# BusAdaptor.net
KiCad netlist of a schematic drawn in Altium Designer
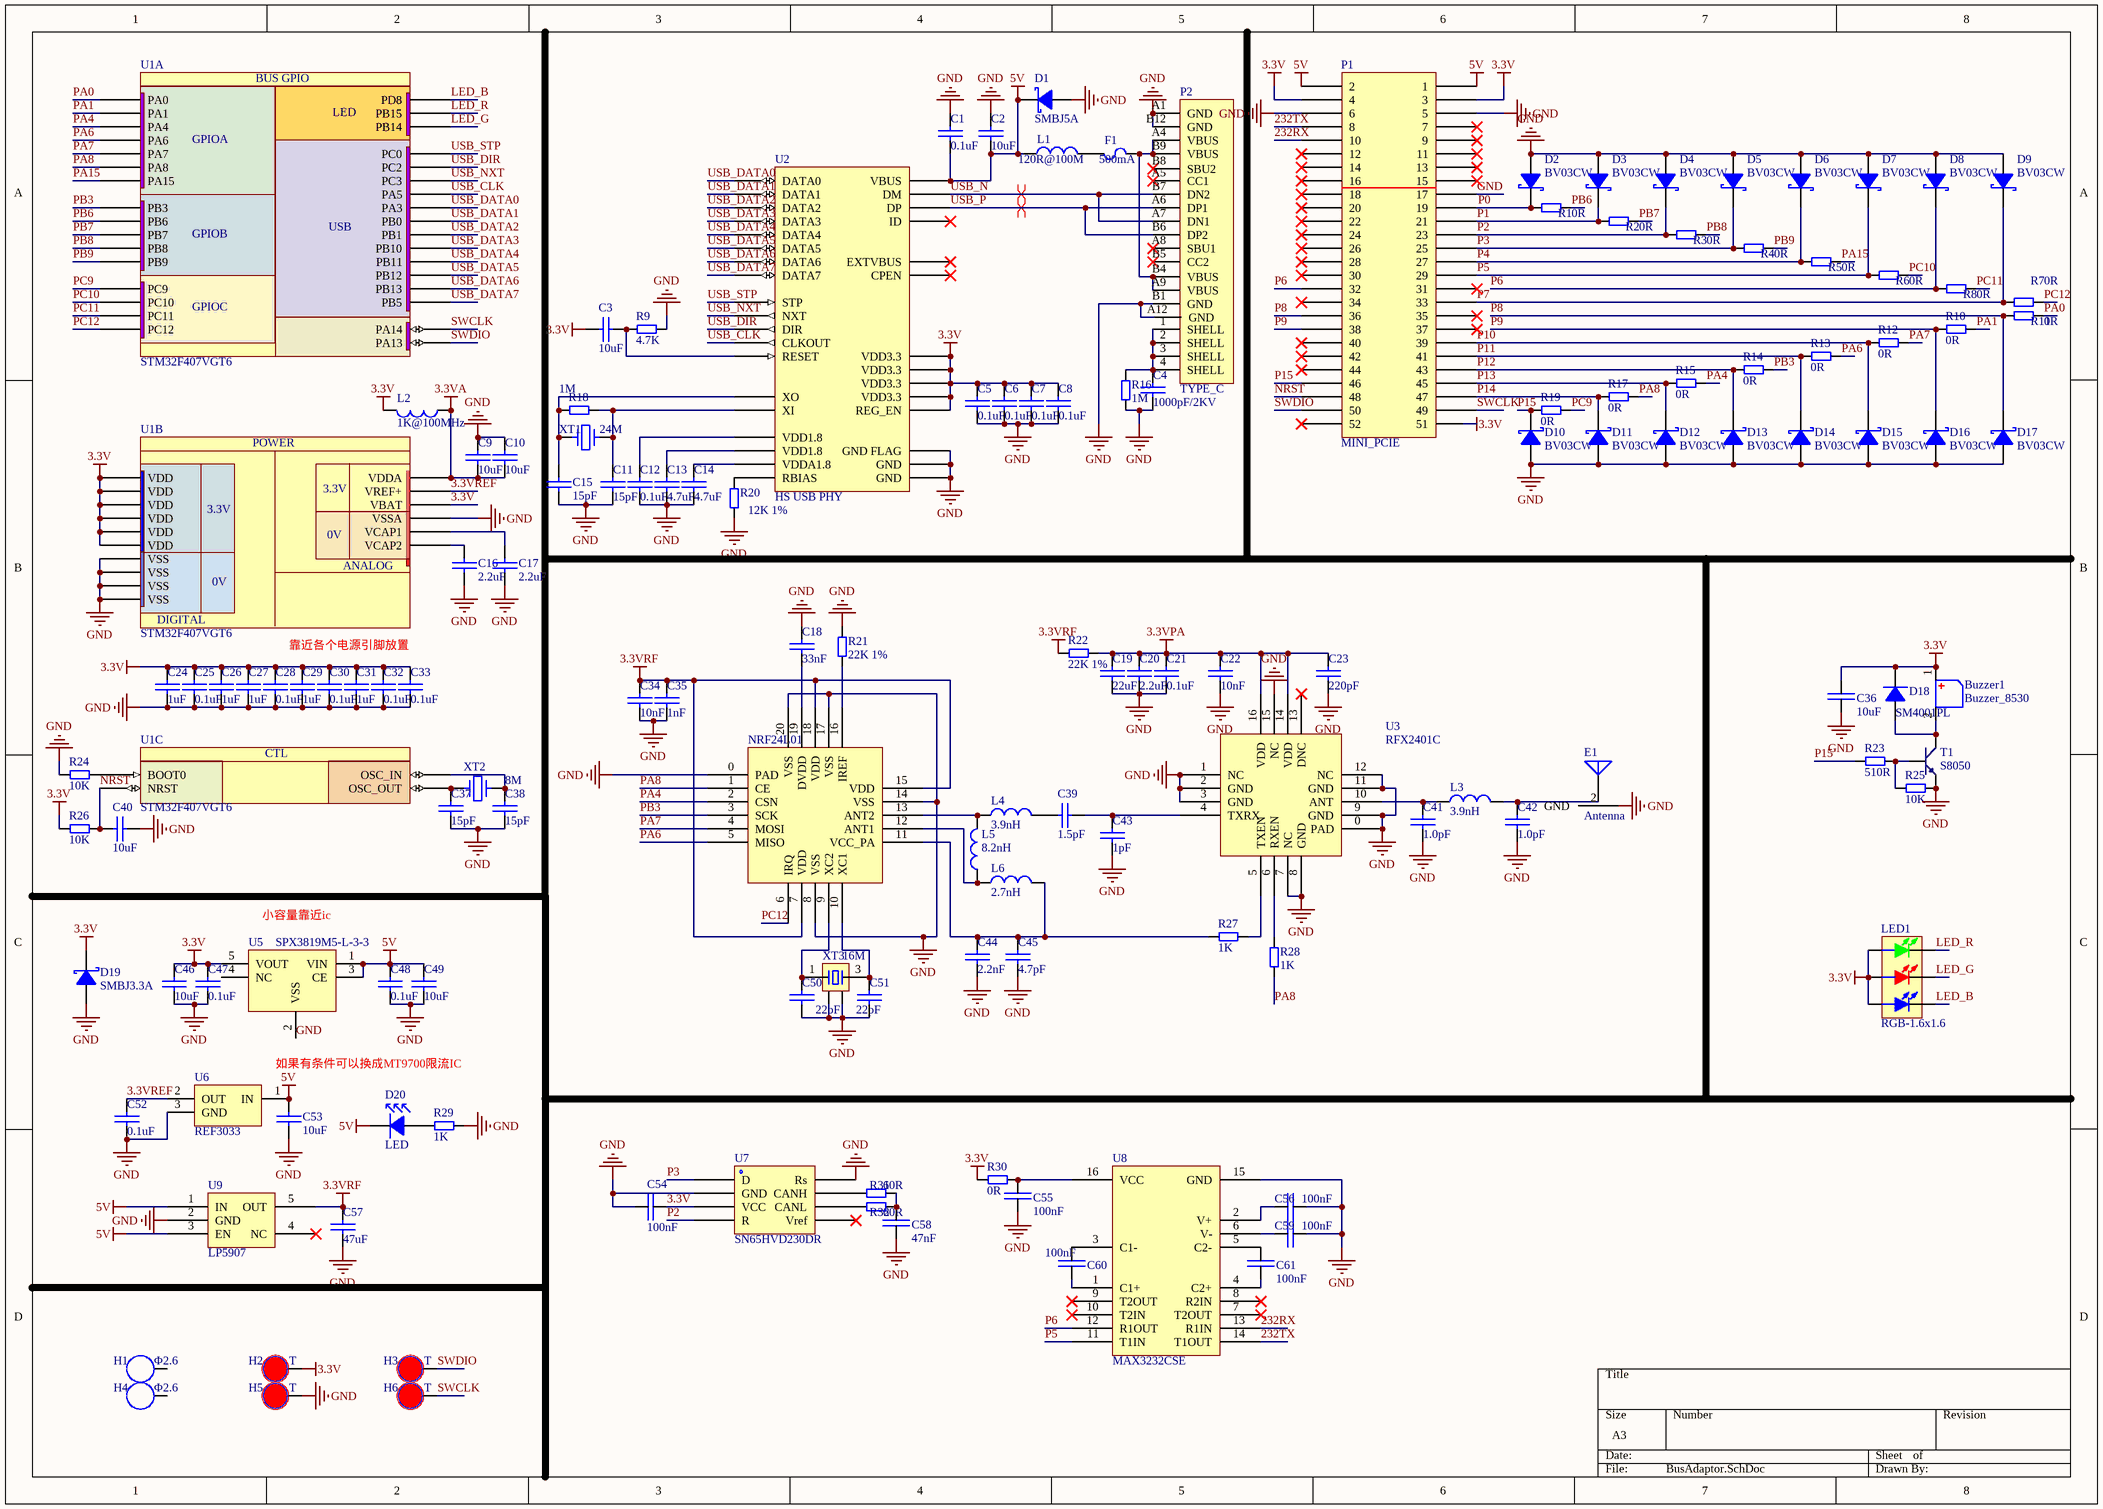
[diagram p0: BusAdaptor.SchDoc]

(export (version "E")
  (design (tool "Eeschema 10.0.6"))
  (components
    (comp (ref "Buzzer1")
      (value "Buzzer_8530")
      (footprint "BUZZER_8530")
      (description "无源蜂鸣器")
      (libsource (lib "BusAdaptor") (part "Buzzer_8530"))
    )
    (comp (ref "C1") (value "0.1uF") (footprint "0201") (libsource (lib "BusAdaptor") (part "C")))
    (comp (ref "C2") (value "10uF") (footprint "0402_C") (libsource (lib "BusAdaptor") (part "C")))
    (comp (ref "C3") (value "10uF") (footprint "0402_C") (libsource (lib "BusAdaptor") (part "C")))
    (comp (ref "C4") (value "1000pF/2KV") (footprint "1206_C") (libsource (lib "BusAdaptor") (part "C")))
    (comp (ref "C5") (value "0.1uF") (footprint "0201") (libsource (lib "BusAdaptor") (part "C")))
    (comp (ref "C6") (value "0.1uF") (footprint "0201") (libsource (lib "BusAdaptor") (part "C")))
    (comp (ref "C7") (value "0.1uF") (footprint "0201") (libsource (lib "BusAdaptor") (part "C")))
    (comp (ref "C8") (value "0.1uF") (footprint "0201") (libsource (lib "BusAdaptor") (part "C")))
    (comp (ref "C9") (value "10uF") (footprint "0402_C") (libsource (lib "BusAdaptor") (part "C")))
    (comp (ref "C10") (value "10uF") (footprint "0402_C") (libsource (lib "BusAdaptor") (part "C")))
    (comp (ref "C11") (value "15pF") (footprint "0201") (libsource (lib "BusAdaptor") (part "C")))
    (comp (ref "C12") (value "0.1uF") (footprint "0201") (libsource (lib "BusAdaptor") (part "C")))
    (comp (ref "C13") (value "4.7uF") (footprint "0402_C") (libsource (lib "BusAdaptor") (part "C")))
    (comp (ref "C14") (value "4.7uF") (footprint "0402_C") (libsource (lib "BusAdaptor") (part "C")))
    (comp (ref "C15") (value "15pF") (footprint "0201") (libsource (lib "BusAdaptor") (part "C")))
    (comp (ref "C16") (value "2.2uF") (footprint "0402_C") (libsource (lib "BusAdaptor") (part "C")))
    (comp (ref "C17") (value "2.2uF") (footprint "0402_C") (libsource (lib "BusAdaptor") (part "C")))
    (comp (ref "C18") (value "33nF") (footprint "0402_C") (libsource (lib "BusAdaptor") (part "C")))
    (comp (ref "C19") (value "22uF") (footprint "0603_C") (libsource (lib "BusAdaptor") (part "C")))
    (comp (ref "C20") (value "2.2uF") (footprint "0402_C") (libsource (lib "BusAdaptor") (part "C")))
    (comp (ref "C21") (value "0.1uF") (footprint "0402_C") (libsource (lib "BusAdaptor") (part "C")))
    (comp (ref "C22") (value "10nF") (footprint "0402_C") (libsource (lib "BusAdaptor") (part "C")))
    (comp (ref "C23") (value "220pF") (footprint "0402_C") (libsource (lib "BusAdaptor") (part "C")))
    (comp (ref "C24") (value "1uF") (footprint "0201") (libsource (lib "BusAdaptor") (part "C")))
    (comp (ref "C25") (value "0.1uF") (footprint "0201") (libsource (lib "BusAdaptor") (part "C")))
    (comp (ref "C26") (value "1uF") (footprint "0201") (libsource (lib "BusAdaptor") (part "C")))
    (comp (ref "C27") (value "1uF") (footprint "0201") (libsource (lib "BusAdaptor") (part "C")))
    (comp (ref "C28") (value "0.1uF") (footprint "0201") (libsource (lib "BusAdaptor") (part "C")))
    (comp (ref "C29") (value "1uF") (footprint "0201") (libsource (lib "BusAdaptor") (part "C")))
    (comp (ref "C30") (value "0.1uF") (footprint "0201") (libsource (lib "BusAdaptor") (part "C")))
    (comp (ref "C31") (value "1uF") (footprint "0201") (libsource (lib "BusAdaptor") (part "C")))
    (comp (ref "C32") (value "0.1uF") (footprint "0201") (libsource (lib "BusAdaptor") (part "C")))
    (comp (ref "C33") (value "0.1uF") (footprint "0201") (libsource (lib "BusAdaptor") (part "C")))
    (comp (ref "C34") (value "10nF") (footprint "0402_C") (libsource (lib "BusAdaptor") (part "C")))
    (comp (ref "C35") (value "1nF") (footprint "0402_C") (libsource (lib "BusAdaptor") (part "C")))
    (comp (ref "C36") (value "10uF") (footprint "0402_C") (libsource (lib "Schlib1") (part "C")))
    (comp (ref "C37") (value "15pF") (footprint "0402_C") (libsource (lib "BusAdaptor") (part "C")))
    (comp (ref "C38") (value "15pF") (footprint "0402_C") (libsource (lib "BusAdaptor") (part "C")))
    (comp (ref "C39") (value "1.5pF") (footprint "0402_C") (libsource (lib "BusAdaptor") (part "C")))
    (comp (ref "C40") (value "10uF") (footprint "0402_C") (libsource (lib "BusAdaptor") (part "C")))
    (comp (ref "C41") (value "1.0pF") (footprint "0402_C") (libsource (lib "BusAdaptor") (part "C")))
    (comp (ref "C42") (value "1.0pF") (footprint "0402_C") (libsource (lib "BusAdaptor") (part "C")))
    (comp (ref "C43") (value "1pF") (footprint "0402_C") (libsource (lib "BusAdaptor") (part "C")))
    (comp (ref "C44") (value "2.2nF") (footprint "0402_C") (libsource (lib "BusAdaptor") (part "C")))
    (comp (ref "C45") (value "4.7pF") (footprint "0402_C") (libsource (lib "BusAdaptor") (part "C")))
    (comp (ref "C46") (value "10uF") (footprint "0402_C") (libsource (lib "BusAdaptor") (part "C")))
    (comp (ref "C47") (value "0.1uF") (footprint "0402_C") (libsource (lib "BusAdaptor") (part "C")))
    (comp (ref "C48") (value "0.1uF") (footprint "0402_C") (libsource (lib "BusAdaptor") (part "C")))
    (comp (ref "C49") (value "10uF") (footprint "0402_C") (libsource (lib "BusAdaptor") (part "C")))
    (comp (ref "C50") (value "22pF") (footprint "0402_C") (libsource (lib "BusAdaptor") (part "C")))
    (comp (ref "C51") (value "22pF") (footprint "0402_C") (libsource (lib "BusAdaptor") (part "C")))
    (comp (ref "C52") (value "0.1uF") (footprint "0402_C") (libsource (lib "BusAdaptor") (part "C")))
    (comp (ref "C53") (value "10uF") (footprint "0402_C") (libsource (lib "BusAdaptor") (part "C")))
    (comp (ref "C54") (value "100nF") (footprint "0402_C") (libsource (lib "Schlib1") (part "C")))
    (comp (ref "C55") (value "100nF") (footprint "0201") (libsource (lib "Schlib1") (part "C")))
    (comp (ref "C56") (value "100nF") (footprint "0201") (libsource (lib "Schlib1") (part "C")))
    (comp (ref "C57") (value "47uF") (footprint "0805_C") (libsource (lib "BusAdaptor") (part "C")))
    (comp (ref "C58") (value "47nF") (footprint "0402_C") (libsource (lib "Schlib1") (part "C")))
    (comp (ref "C59") (value "100nF") (footprint "0201") (libsource (lib "Schlib1") (part "C")))
    (comp (ref "C60") (value "100nF") (footprint "0201") (libsource (lib "Schlib1") (part "C")))
    (comp (ref "C61") (value "100nF") (footprint "0201") (libsource (lib "Schlib1") (part "C")))
    (comp (ref "D1")
      (value "SMBJ5A")
      (footprint "SMB")
      (description "BV03CW")
      (libsource (lib "BusAdaptor") (part "TVS"))
    )
    (comp (ref "D2") (value "BV03CW") (footprint "SOD323") (libsource (lib "BusAdaptor") (part "TVS")))
    (comp (ref "D3") (value "BV03CW") (footprint "SOD323") (libsource (lib "BusAdaptor") (part "TVS")))
    (comp (ref "D4") (value "BV03CW") (footprint "SOD323") (libsource (lib "BusAdaptor") (part "TVS")))
    (comp (ref "D5") (value "BV03CW") (footprint "SOD323") (libsource (lib "BusAdaptor") (part "TVS")))
    (comp (ref "D6") (value "BV03CW") (footprint "SOD323") (libsource (lib "BusAdaptor") (part "TVS")))
    (comp (ref "D7") (value "BV03CW") (footprint "SOD323") (libsource (lib "BusAdaptor") (part "TVS")))
    (comp (ref "D8") (value "BV03CW") (footprint "SOD323") (libsource (lib "BusAdaptor") (part "TVS")))
    (comp (ref "D9") (value "BV03CW") (footprint "SOD323") (libsource (lib "BusAdaptor") (part "TVS")))
    (comp (ref "D10") (value "BV03CW") (footprint "SOD323") (libsource (lib "BusAdaptor") (part "TVS")))
    (comp (ref "D11") (value "BV03CW") (footprint "SOD323") (libsource (lib "BusAdaptor") (part "TVS")))
    (comp (ref "D12") (value "BV03CW") (footprint "SOD323") (libsource (lib "BusAdaptor") (part "TVS")))
    (comp (ref "D13") (value "BV03CW") (footprint "SOD323") (libsource (lib "BusAdaptor") (part "TVS")))
    (comp (ref "D14") (value "BV03CW") (footprint "SOD323") (libsource (lib "BusAdaptor") (part "TVS")))
    (comp (ref "D15") (value "BV03CW") (footprint "SOD323") (libsource (lib "BusAdaptor") (part "TVS")))
    (comp (ref "D16") (value "BV03CW") (footprint "SOD323") (libsource (lib "BusAdaptor") (part "TVS")))
    (comp (ref "D17") (value "BV03CW") (footprint "SOD323") (libsource (lib "BusAdaptor") (part "TVS")))
    (comp (ref "D18")
      (value "SM4001PL")
      (footprint "SOD-123FL")
      (description "二极管")
      (libsource (lib "BusAdaptor") (part "Diode"))
    )
    (comp (ref "D19")
      (value "SMBJ3.3A")
      (footprint "SMB")
      (description "BV03CW")
      (libsource (lib "BusAdaptor") (part "TVS"))
    )
    (comp (ref "D20") (value "LED") (footprint "0603_L") (libsource (lib "BusAdaptor") (part "LED")))
    (comp (ref "E1")
      (value "Antenna")
      (footprint "IPEX")
      (description "Generic Antenna")
      (fields (field (name "PUBLISHER") "Altium Limited"))
      (libsource (lib "BusAdaptor") (part "Antenna"))
    )
    (comp (ref "F1")
      (value "500mA")
      (footprint "0805_R")
      (description "FUSE")
      (libsource (lib "BusAdaptor") (part "FUSE"))
    )
    (comp (ref "H1") (value "Φ2.6") (footprint "HOLD") (libsource (lib "BusAdaptor") (part "MECHANICAL")))
    (comp (ref "H2") (value "T") (footprint "testpoint") (libsource (lib "BusAdaptor") (part "TEST_POINT")))
    (comp (ref "H3") (value "T") (footprint "testpoint") (libsource (lib "BusAdaptor") (part "TEST_POINT")))
    (comp (ref "H4") (value "Φ2.6") (footprint "HOLD") (libsource (lib "BusAdaptor") (part "MECHANICAL")))
    (comp (ref "H5") (value "T") (footprint "testpoint") (libsource (lib "BusAdaptor") (part "TEST_POINT")))
    (comp (ref "H6") (value "T") (footprint "testpoint") (libsource (lib "BusAdaptor") (part "TEST_POINT")))
    (comp (ref "L1") (value "120R@100M") (footprint "0603_L") (libsource (lib "BusAdaptor") (part "L")))
    (comp (ref "L2") (value "1K@100MHz") (footprint "0603_L") (libsource (lib "BusAdaptor") (part "L")))
    (comp (ref "L3") (value "3.9nH") (footprint "0402_L") (libsource (lib "BusAdaptor") (part "L")))
    (comp (ref "L4") (value "3.9nH") (footprint "0402_L") (libsource (lib "BusAdaptor") (part "L")))
    (comp (ref "L5") (value "8.2nH") (footprint "0402_L") (libsource (lib "BusAdaptor") (part "L")))
    (comp (ref "L6") (value "2.7nH") (footprint "0402_L") (libsource (lib "BusAdaptor") (part "L")))
    (comp (ref "LED1")
      (value "RGB-1.6x1.6")
      (footprint "RGB-1.6x1.6")
      (description "3528三基色LED")
      (libsource (lib "BusAdaptor") (part "LED-RGB 3528"))
    )
    (comp (ref "NRF24L01")
      (value "NRF24L01")
      (footprint "QFN-20_4x4x05P")
      (libsource (lib "BusAdaptor") (part "NRF24L01"))
    )
    (comp (ref "P1")
      (value "MINI_PCIE")
      (footprint "MINIPCIE")
      (libsource (lib "BusAdaptor") (part "MINI_PCIE"))
    )
    (comp (ref "P2") (value "TYPE_C") (footprint "TYPE-C-TOP") (libsource (lib "BusAdaptor") (part "USB_C")))
    (comp (ref "R1")
      (value "0R")
      (footprint "0402_R")
      (description "resistor")
      (libsource (lib "BusAdaptor") (part "R"))
    )
    (comp (ref "R2")
      (value "0R")
      (footprint "0402_R")
      (description "resistor")
      (libsource (lib "BusAdaptor") (part "R"))
    )
    (comp (ref "R3")
      (value "0R")
      (footprint "0402_R")
      (description "resistor")
      (libsource (lib "BusAdaptor") (part "R"))
    )
    (comp (ref "R4")
      (value "0R")
      (footprint "0402_R")
      (description "resistor")
      (libsource (lib "BusAdaptor") (part "R"))
    )
    (comp (ref "R5")
      (value "0R")
      (footprint "0402_R")
      (description "resistor")
      (libsource (lib "BusAdaptor") (part "R"))
    )
    (comp (ref "R6")
      (value "0R")
      (footprint "0402_R")
      (description "resistor")
      (libsource (lib "BusAdaptor") (part "R"))
    )
    (comp (ref "R7")
      (value "0R")
      (footprint "0402_R")
      (description "resistor")
      (libsource (lib "BusAdaptor") (part "R"))
    )
    (comp (ref "R8")
      (value "0R")
      (footprint "0402_R")
      (description "resistor")
      (libsource (lib "BusAdaptor") (part "R"))
    )
    (comp (ref "R9")
      (value "4.7K")
      (footprint "0402_R")
      (description "resistor")
      (libsource (lib "BusAdaptor") (part "R"))
    )
    (comp (ref "R10")
      (value "0R")
      (footprint "0402_R")
      (description "resistor")
      (libsource (lib "BusAdaptor") (part "R"))
    )
    (comp (ref "R11")
      (value "0R")
      (footprint "0402_R")
      (description "resistor")
      (libsource (lib "BusAdaptor") (part "R"))
    )
    (comp (ref "R12")
      (value "0R")
      (footprint "0402_R")
      (description "resistor")
      (libsource (lib "BusAdaptor") (part "R"))
    )
    (comp (ref "R13")
      (value "0R")
      (footprint "0402_R")
      (description "resistor")
      (libsource (lib "BusAdaptor") (part "R"))
    )
    (comp (ref "R14")
      (value "0R")
      (footprint "0402_R")
      (description "resistor")
      (libsource (lib "BusAdaptor") (part "R"))
    )
    (comp (ref "R15")
      (value "0R")
      (footprint "0402_R")
      (description "resistor")
      (libsource (lib "BusAdaptor") (part "R"))
    )
    (comp (ref "R16")
      (value "1M")
      (footprint "0201")
      (description "resistor")
      (libsource (lib "BusAdaptor") (part "R"))
    )
    (comp (ref "R17")
      (value "0R")
      (footprint "0402_R")
      (description "resistor")
      (libsource (lib "BusAdaptor") (part "R"))
    )
    (comp (ref "R18")
      (value "1M")
      (footprint "0201")
      (description "resistor")
      (libsource (lib "BusAdaptor") (part "R"))
    )
    (comp (ref "R19")
      (value "0R")
      (footprint "0402_R")
      (description "resistor")
      (libsource (lib "BusAdaptor") (part "R"))
    )
    (comp (ref "R20")
      (value "12K 1%")
      (footprint "0402_R")
      (description "resistor")
      (libsource (lib "BusAdaptor") (part "R"))
    )
    (comp (ref "R21")
      (value "22K 1%")
      (footprint "0402_R")
      (description "resistor")
      (libsource (lib "BusAdaptor") (part "R"))
    )
    (comp (ref "R22")
      (value "22K 1%")
      (footprint "0402_R")
      (description "resistor")
      (libsource (lib "BusAdaptor") (part "R"))
    )
    (comp (ref "R23")
      (value "510R")
      (footprint "0402_R")
      (description "resistor")
      (libsource (lib "BusAdaptor") (part "R"))
    )
    (comp (ref "R24")
      (value "10K")
      (footprint "0402_R")
      (description "resistor")
      (libsource (lib "BusAdaptor") (part "R"))
    )
    (comp (ref "R25")
      (value "10K")
      (footprint "0402_R")
      (description "resistor")
      (libsource (lib "BusAdaptor") (part "R"))
    )
    (comp (ref "R26")
      (value "10K")
      (footprint "0402_R")
      (description "resistor")
      (libsource (lib "BusAdaptor") (part "R"))
    )
    (comp (ref "R27")
      (value "1K")
      (footprint "0402_R")
      (description "resistor")
      (libsource (lib "BusAdaptor") (part "R"))
    )
    (comp (ref "R28")
      (value "1K")
      (footprint "0402_R")
      (description "resistor")
      (libsource (lib "BusAdaptor") (part "R"))
    )
    (comp (ref "R29")
      (value "1K")
      (footprint "0402_R")
      (description "resistor")
      (libsource (lib "BusAdaptor") (part "R"))
    )
    (comp (ref "R30")
      (value "0R")
      (footprint "0201")
      (description "resistor")
      (libsource (lib "BusAdaptor") (part "R"))
    )
    (comp (ref "R31")
      (value "60R")
      (footprint "0402_R")
      (description "resistor")
      (libsource (lib "BusAdaptor") (part "R"))
    )
    (comp (ref "R32")
      (value "60R")
      (footprint "0402_R")
      (description "resistor")
      (libsource (lib "BusAdaptor") (part "R"))
    )
    (comp (ref "T1")
      (value "S8050")
      (footprint "SOT-23(SOT-23-3)")
      (description "NPN")
      (libsource (lib "BusAdaptor") (part "Triode"))
    )
    (comp (ref "U1")
      (value "STM32F407VGT6")
      (footprint "TQFP-100")
      (description "ARM Cortex-M4 32b MCU+FPU, 1024 kB Flash, 192+4 kB RAM,82 I/Os, 100-pin LQFP")
      (libsource (lib "BusAdaptor") (part "STM32F407VGT6"))
    )
    (comp (ref "U2")
      (value "HS USB PHY")
      (footprint "QFN50P500X500X100-32N")
      (description "高速USB外置PHY")
      (libsource (lib "BusAdaptor") (part "USB3300"))
    )
    (comp (ref "U3")
      (value "RFX2401C")
      (footprint "RFX2401C")
      (libsource (lib "BusAdaptor") (part "RFX2401C"))
    )
    (comp (ref "U5")
      (value "SPX3819M5-L-3-3")
      (footprint "SOT-23-5")
      (libsource (lib "BusAdaptor") (part "ME6211"))
    )
    (comp (ref "U6")
      (value "REF3033")
      (footprint "SOT-23(SOT-23-3)")
      (description "REF3033电压参考源")
      (libsource (lib "BusAdaptor") (part "REF3033"))
    )
    (comp (ref "U7") (value "SN65HVD230DR") (libsource (lib "BusAdaptor") (part "SN65HVD230DR")))
    (comp (ref "U8")
      (value "MAX3232CSE")
      (footprint "SOIC-16_150mil")
      (libsource (lib "BusAdaptor") (part "RS3232"))
    )
    (comp (ref "U9") (value "LP5907") (footprint "SOT-23-5") (libsource (lib "BusAdaptor") (part "LP5907")))
    (comp (ref "XT1")
      (value "24M")
      (footprint "CRYSTAL-SMD-5032")
      (description "晶振")
      (libsource (lib "BusAdaptor") (part "XTAL"))
    )
    (comp (ref "XT2")
      (value "8M")
      (footprint "CRYSTAL-SMD-5032")
      (description "晶振")
      (libsource (lib "BusAdaptor") (part "XTAL"))
    )
    (comp (ref "XT3")
      (value "16M")
      (footprint "OSC 3225-4P")
      (description "4脚无源晶振")
      (libsource (lib "BusAdaptor") (part "XTAL-4P"))
    )
  )
  (nets
    (net (code "1") (name "/3.3VREF") (class "Default")
      (node (ref "C52") (pin "2") (pinfunction "2_2") (pintype "passive"))
      (node (ref "U1") (pin "21") (pinfunction "VREF+_21") (pintype "power_in"))
      (node (ref "U6") (pin "2") (pinfunction "OUT_2") (pintype "passive"))
    )
    (net (code "2") (name "/232RX") (class "Default")
      (node (ref "P1") (pin "10") (pinfunction "10_10") (pintype "passive"))
      (node (ref "U8") (pin "13") (pinfunction "R1IN_13") (pintype "passive"))
    )
    (net (code "3") (name "/232TX") (class "Default")
      (node (ref "P1") (pin "8") (pinfunction "8_8") (pintype "passive"))
      (node (ref "U8") (pin "14") (pinfunction "T1OUT_14") (pintype "passive"))
    )
    (net (code "4") (name "/LED_B") (class "Default")
      (node (ref "LED1") (pin "5") (pinfunction "BULE_K_5") (pintype "passive"))
      (node (ref "U1") (pin "55") (pinfunction "PD8_55") (pintype "passive"))
    )
    (net (code "5") (name "/LED_G") (class "Default")
      (node (ref "LED1") (pin "3") (pinfunction "RED_K_3") (pintype "passive"))
      (node (ref "U1") (pin "53") (pinfunction "PB14_53") (pintype "passive"))
    )
    (net (code "6") (name "/LED_R") (class "Default")
      (node (ref "LED1") (pin "1") (pinfunction "GREEN_K_1") (pintype "passive"))
      (node (ref "U1") (pin "54") (pinfunction "PB15_54") (pintype "passive"))
    )
    (net (code "7") (name "/NRST") (class "Default")
      (node (ref "C40") (pin "2") (pinfunction "2_2") (pintype "passive"))
      (node (ref "P1") (pin "48") (pinfunction "48_48") (pintype "passive"))
      (node (ref "R26") (pin "2") (pinfunction "2_2") (pintype "passive"))
      (node (ref "U1") (pin "14") (pinfunction "NRST_14") (pintype "bidirectional"))
    )
    (net (code "8") (name "/P0") (class "Default")
      (node (ref "D2") (pin "2") (pinfunction "K_2") (pintype "passive"))
      (node (ref "P1") (pin "19") (pinfunction "19_19") (pintype "passive"))
      (node (ref "R1") (pin "1") (pinfunction "1_1") (pintype "passive"))
    )
    (net (code "9") (name "/P1") (class "Default")
      (node (ref "D3") (pin "2") (pinfunction "K_2") (pintype "passive"))
      (node (ref "P1") (pin "21") (pinfunction "21_21") (pintype "passive"))
      (node (ref "R2") (pin "1") (pinfunction "1_1") (pintype "passive"))
    )
    (net (code "10") (name "/P2") (class "Default")
      (node (ref "D4") (pin "2") (pinfunction "K_2") (pintype "passive"))
      (node (ref "P1") (pin "23") (pinfunction "23_23") (pintype "passive"))
      (node (ref "R3") (pin "1") (pinfunction "1_1") (pintype "passive"))
      (node (ref "U7") (pin "4") (pinfunction "R_4") (pintype "passive"))
    )
    (net (code "11") (name "/P3") (class "Default")
      (node (ref "D5") (pin "2") (pinfunction "K_2") (pintype "passive"))
      (node (ref "P1") (pin "25") (pinfunction "25_25") (pintype "passive"))
      (node (ref "R4") (pin "1") (pinfunction "1_1") (pintype "passive"))
      (node (ref "U7") (pin "1") (pinfunction "D_1") (pintype "passive"))
    )
    (net (code "12") (name "/P4") (class "Default")
      (node (ref "D6") (pin "2") (pinfunction "K_2") (pintype "passive"))
      (node (ref "P1") (pin "27") (pinfunction "27_27") (pintype "passive"))
      (node (ref "R5") (pin "1") (pinfunction "1_1") (pintype "passive"))
    )
    (net (code "13") (name "/P5") (class "Default")
      (node (ref "D7") (pin "2") (pinfunction "K_2") (pintype "passive"))
      (node (ref "P1") (pin "29") (pinfunction "29_29") (pintype "passive"))
      (node (ref "R6") (pin "1") (pinfunction "1_1") (pintype "passive"))
      (node (ref "U8") (pin "11") (pinfunction "T1IN_11") (pintype "passive"))
    )
    (net (code "14") (name "/P6") (class "Default")
      (node (ref "D8") (pin "2") (pinfunction "K_2") (pintype "passive"))
      (node (ref "P1") (pin "32") (pinfunction "32_32") (pintype "passive"))
      (node (ref "R8") (pin "1") (pinfunction "1_1") (pintype "passive"))
      (node (ref "U8") (pin "12") (pinfunction "R1OUT_12") (pintype "passive"))
    )
    (net (code "15") (name "/P7") (class "Default")
      (node (ref "D9") (pin "2") (pinfunction "K_2") (pintype "passive"))
      (node (ref "P1") (pin "33") (pinfunction "33_33") (pintype "passive"))
      (node (ref "R7") (pin "1") (pinfunction "1_1") (pintype "passive"))
    )
    (net (code "16") (name "/P8") (class "Default")
      (node (ref "D17") (pin "2") (pinfunction "K_2") (pintype "passive"))
      (node (ref "P1") (pin "36") (pinfunction "36_36") (pintype "passive"))
      (node (ref "R11") (pin "1") (pinfunction "1_1") (pintype "passive"))
    )
    (net (code "17") (name "/P9") (class "Default")
      (node (ref "D16") (pin "2") (pinfunction "K_2") (pintype "passive"))
      (node (ref "P1") (pin "38") (pinfunction "38_38") (pintype "passive"))
      (node (ref "R10") (pin "1") (pinfunction "1_1") (pintype "passive"))
    )
    (net (code "18") (name "/P10") (class "Default")
      (node (ref "D15") (pin "2") (pinfunction "K_2") (pintype "passive"))
      (node (ref "P1") (pin "39") (pinfunction "39_39") (pintype "passive"))
      (node (ref "R12") (pin "1") (pinfunction "1_1") (pintype "passive"))
    )
    (net (code "19") (name "/P11") (class "Default")
      (node (ref "D14") (pin "2") (pinfunction "K_2") (pintype "passive"))
      (node (ref "P1") (pin "41") (pinfunction "41_41") (pintype "passive"))
      (node (ref "R13") (pin "1") (pinfunction "1_1") (pintype "passive"))
    )
    (net (code "20") (name "/P12") (class "Default")
      (node (ref "D13") (pin "2") (pinfunction "K_2") (pintype "passive"))
      (node (ref "P1") (pin "43") (pinfunction "43_43") (pintype "passive"))
      (node (ref "R14") (pin "1") (pinfunction "1_1") (pintype "passive"))
    )
    (net (code "21") (name "/P13") (class "Default")
      (node (ref "D12") (pin "2") (pinfunction "K_2") (pintype "passive"))
      (node (ref "P1") (pin "45") (pinfunction "45_45") (pintype "passive"))
      (node (ref "R15") (pin "1") (pinfunction "1_1") (pintype "passive"))
    )
    (net (code "22") (name "/P14") (class "Default")
      (node (ref "D11") (pin "2") (pinfunction "K_2") (pintype "passive"))
      (node (ref "P1") (pin "47") (pinfunction "47_47") (pintype "passive"))
      (node (ref "R17") (pin "1") (pinfunction "1_1") (pintype "passive"))
    )
    (net (code "23") (name "/P15") (class "Default")
      (node (ref "D10") (pin "2") (pinfunction "K_2") (pintype "passive"))
      (node (ref "P1") (pin "46") (pinfunction "46_46") (pintype "passive"))
      (node (ref "R19") (pin "1") (pinfunction "1_1") (pintype "passive"))
      (node (ref "R23") (pin "1") (pinfunction "1_1") (pintype "passive"))
    )
    (net (code "24") (name "/PA0") (class "Default")
      (node (ref "R11") (pin "2") (pinfunction "2_2") (pintype "passive"))
      (node (ref "U1") (pin "23") (pinfunction "PA0_23") (pintype "passive"))
    )
    (net (code "25") (name "/PA1") (class "Default")
      (node (ref "R10") (pin "2") (pinfunction "2_2") (pintype "passive"))
      (node (ref "U1") (pin "24") (pinfunction "PA1_24") (pintype "passive"))
    )
    (net (code "26") (name "/PA4") (class "Default")
      (node (ref "NRF24L01") (pin "2") (pinfunction "CSN_2") (pintype "passive"))
      (node (ref "R15") (pin "2") (pinfunction "2_2") (pintype "passive"))
      (node (ref "U1") (pin "29") (pinfunction "PA4_29") (pintype "passive"))
    )
    (net (code "27") (name "/PA6") (class "Default")
      (node (ref "NRF24L01") (pin "5") (pinfunction "MISO_5") (pintype "passive"))
      (node (ref "R13") (pin "2") (pinfunction "2_2") (pintype "passive"))
      (node (ref "U1") (pin "31") (pinfunction "PA6_31") (pintype "passive"))
    )
    (net (code "28") (name "/PA7") (class "Default")
      (node (ref "NRF24L01") (pin "4") (pinfunction "MOSI_4") (pintype "passive"))
      (node (ref "R12") (pin "2") (pinfunction "2_2") (pintype "passive"))
      (node (ref "U1") (pin "32") (pinfunction "PA7_32") (pintype "passive"))
    )
    (net (code "29") (name "/PA8") (class "Default")
      (node (ref "NRF24L01") (pin "1") (pinfunction "CE_1") (pintype "passive"))
      (node (ref "R17") (pin "2") (pinfunction "2_2") (pintype "passive"))
      (node (ref "R28") (pin "1") (pinfunction "1_1") (pintype "passive"))
      (node (ref "U1") (pin "67") (pinfunction "PA8_67") (pintype "passive"))
    )
    (net (code "30") (name "/PA15") (class "Default")
      (node (ref "R5") (pin "2") (pinfunction "2_2") (pintype "passive"))
      (node (ref "U1") (pin "77") (pinfunction "PA15_77") (pintype "passive"))
    )
    (net (code "31") (name "/PB3") (class "Default")
      (node (ref "NRF24L01") (pin "3") (pinfunction "SCK_3") (pintype "passive"))
      (node (ref "R14") (pin "2") (pinfunction "2_2") (pintype "passive"))
      (node (ref "U1") (pin "89") (pinfunction "PB3_89") (pintype "passive"))
    )
    (net (code "32") (name "/PB6") (class "Default")
      (node (ref "R1") (pin "2") (pinfunction "2_2") (pintype "passive"))
      (node (ref "U1") (pin "92") (pinfunction "PB6_92") (pintype "passive"))
    )
    (net (code "33") (name "/PB7") (class "Default")
      (node (ref "R2") (pin "2") (pinfunction "2_2") (pintype "passive"))
      (node (ref "U1") (pin "93") (pinfunction "PB7_93") (pintype "passive"))
    )
    (net (code "34") (name "/PB8") (class "Default")
      (node (ref "R3") (pin "2") (pinfunction "2_2") (pintype "passive"))
      (node (ref "U1") (pin "95") (pinfunction "PB8_95") (pintype "passive"))
    )
    (net (code "35") (name "/PB9") (class "Default")
      (node (ref "R4") (pin "2") (pinfunction "2_2") (pintype "passive"))
      (node (ref "U1") (pin "96") (pinfunction "PB9_96") (pintype "passive"))
    )
    (net (code "36") (name "/PC9") (class "Default")
      (node (ref "R19") (pin "2") (pinfunction "2_2") (pintype "passive"))
      (node (ref "U1") (pin "66") (pinfunction "PC9_66") (pintype "passive"))
    )
    (net (code "37") (name "/PC10") (class "Default")
      (node (ref "R6") (pin "2") (pinfunction "2_2") (pintype "passive"))
      (node (ref "U1") (pin "78") (pinfunction "PC10_78") (pintype "passive"))
    )
    (net (code "38") (name "/PC11") (class "Default")
      (node (ref "R8") (pin "2") (pinfunction "2_2") (pintype "passive"))
      (node (ref "U1") (pin "79") (pinfunction "PC11_79") (pintype "passive"))
    )
    (net (code "39") (name "/PC12") (class "Default")
      (node (ref "NRF24L01") (pin "6") (pinfunction "IRQ_6") (pintype "passive"))
      (node (ref "R7") (pin "2") (pinfunction "2_2") (pintype "passive"))
      (node (ref "U1") (pin "80") (pinfunction "PC12_80") (pintype "passive"))
    )
    (net (code "40") (name "/SWCLK") (class "Default")
      (node (ref "H6") (pin "1") (pinfunction "1_1") (pintype "passive"))
      (node (ref "P1") (pin "49") (pinfunction "49_49") (pintype "passive"))
      (node (ref "U1") (pin "76") (pinfunction "PA14_76") (pintype "bidirectional"))
    )
    (net (code "41") (name "/SWDIO") (class "Default")
      (node (ref "H3") (pin "1") (pinfunction "1_1") (pintype "passive"))
      (node (ref "P1") (pin "50") (pinfunction "50_50") (pintype "passive"))
      (node (ref "U1") (pin "72") (pinfunction "PA13_72") (pintype "bidirectional"))
    )
    (net (code "42") (name "/USB_CLK") (class "Default")
      (node (ref "U1") (pin "30") (pinfunction "PA5_30") (pintype "passive"))
      (node (ref "U2") (pin "14") (pinfunction "CLKOUT_14") (pintype "output"))
    )
    (net (code "43") (name "/USB_DATA0") (class "Default")
      (node (ref "U1") (pin "26") (pinfunction "PA3_26") (pintype "passive"))
      (node (ref "U2") (pin "24") (pinfunction "DATA0_24") (pintype "bidirectional"))
    )
    (net (code "44") (name "/USB_DATA1") (class "Default")
      (node (ref "U1") (pin "35") (pinfunction "PB0_35") (pintype "passive"))
      (node (ref "U2") (pin "23") (pinfunction "DATA1_23") (pintype "bidirectional"))
    )
    (net (code "45") (name "/USB_DATA2") (class "Default")
      (node (ref "U1") (pin "36") (pinfunction "PB1_36") (pintype "passive"))
      (node (ref "U2") (pin "22") (pinfunction "DATA2_22") (pintype "bidirectional"))
    )
    (net (code "46") (name "/USB_DATA3") (class "Default")
      (node (ref "U1") (pin "47") (pinfunction "PB10_47") (pintype "passive"))
      (node (ref "U2") (pin "21") (pinfunction "DATA3_21") (pintype "bidirectional"))
    )
    (net (code "47") (name "/USB_DATA4") (class "Default")
      (node (ref "U1") (pin "48") (pinfunction "PB11_48") (pintype "passive"))
      (node (ref "U2") (pin "20") (pinfunction "DATA4_20") (pintype "bidirectional"))
    )
    (net (code "48") (name "/USB_DATA5") (class "Default")
      (node (ref "U1") (pin "51") (pinfunction "PB12_51") (pintype "passive"))
      (node (ref "U2") (pin "19") (pinfunction "DATA5_19") (pintype "bidirectional"))
    )
    (net (code "49") (name "/USB_DATA6") (class "Default")
      (node (ref "U1") (pin "52") (pinfunction "PB13_52") (pintype "passive"))
      (node (ref "U2") (pin "18") (pinfunction "DATA6_18") (pintype "bidirectional"))
    )
    (net (code "50") (name "/USB_DATA7") (class "Default")
      (node (ref "U1") (pin "91") (pinfunction "PB5_91") (pintype "passive"))
      (node (ref "U2") (pin "17") (pinfunction "DATA7_17") (pintype "bidirectional"))
    )
    (net (code "51") (name "/USB_DIR") (class "Default")
      (node (ref "U1") (pin "17") (pinfunction "PC2_17") (pintype "passive"))
      (node (ref "U2") (pin "12") (pinfunction "DIR_12") (pintype "output"))
    )
    (net (code "52") (name "/USB_N") (class "Default")
      (node (ref "P2") (pin "A7") (pinfunction "DN1_A7") (pintype "passive"))
      (node (ref "P2") (pin "B7") (pinfunction "DN2_B7") (pintype "passive"))
      (node (ref "U2") (pin "8") (pinfunction "DM_8") (pintype "passive"))
    )
    (net (code "53") (name "/USB_NXT") (class "Default")
      (node (ref "U1") (pin "18") (pinfunction "PC3_18") (pintype "passive"))
      (node (ref "U2") (pin "11") (pinfunction "NXT_11") (pintype "output"))
    )
    (net (code "54") (name "/USB_P") (class "Default")
      (node (ref "P2") (pin "A6") (pinfunction "DP1_A6") (pintype "passive"))
      (node (ref "P2") (pin "B6") (pinfunction "DP2_B6") (pintype "passive"))
      (node (ref "U2") (pin "7") (pinfunction "DP_7") (pintype "passive"))
    )
    (net (code "55") (name "/USB_STP") (class "Default")
      (node (ref "U1") (pin "15") (pinfunction "PC0_15") (pintype "passive"))
      (node (ref "U2") (pin "13") (pinfunction "STP_13") (pintype "input"))
    )
    (net (code "56") (name "3.3V") (class "Default")
      (node (ref "Buzzer1") (pin "1") (pinfunction "1_1") (pintype "passive"))
      (node (ref "C24") (pin "2") (pinfunction "2_2") (pintype "passive"))
      (node (ref "C25") (pin "2") (pinfunction "2_2") (pintype "passive"))
      (node (ref "C26") (pin "2") (pinfunction "2_2") (pintype "passive"))
      (node (ref "C27") (pin "2") (pinfunction "2_2") (pintype "passive"))
      (node (ref "C28") (pin "2") (pinfunction "2_2") (pintype "passive"))
      (node (ref "C29") (pin "2") (pinfunction "2_2") (pintype "passive"))
      (node (ref "C3") (pin "2") (pinfunction "2_2") (pintype "passive"))
      (node (ref "C30") (pin "2") (pinfunction "2_2") (pintype "passive"))
      (node (ref "C31") (pin "2") (pinfunction "2_2") (pintype "passive"))
      (node (ref "C32") (pin "2") (pinfunction "2_2") (pintype "passive"))
      (node (ref "C33") (pin "2") (pinfunction "2_2") (pintype "passive"))
      (node (ref "C36") (pin "2") (pinfunction "2_2") (pintype "passive"))
      (node (ref "C46") (pin "2") (pinfunction "2_2") (pintype "passive"))
      (node (ref "C47") (pin "2") (pinfunction "2_2") (pintype "passive"))
      (node (ref "C5") (pin "2") (pinfunction "2_2") (pintype "passive"))
      (node (ref "C54") (pin "1") (pinfunction "1_1") (pintype "passive"))
      (node (ref "C6") (pin "2") (pinfunction "2_2") (pintype "passive"))
      (node (ref "C7") (pin "2") (pinfunction "2_2") (pintype "passive"))
      (node (ref "C8") (pin "2") (pinfunction "2_2") (pintype "passive"))
      (node (ref "D18") (pin "2") (pinfunction "K_2") (pintype "passive"))
      (node (ref "D19") (pin "2") (pinfunction "K_2") (pintype "passive"))
      (node (ref "H2") (pin "1") (pinfunction "1_1") (pintype "passive"))
      (node (ref "L2") (pin "2") (pinfunction "2_2") (pintype "passive"))
      (node (ref "LED1") (pin "2") (pinfunction "A_2") (pintype "passive"))
      (node (ref "LED1") (pin "4") (pinfunction "A_4") (pintype "passive"))
      (node (ref "LED1") (pin "6") (pinfunction "A_6") (pintype "passive"))
      (node (ref "P1") (pin "3") (pinfunction "3_3") (pintype "passive"))
      (node (ref "P1") (pin "4") (pinfunction "4_4") (pintype "passive"))
      (node (ref "P1") (pin "51") (pinfunction "51_51") (pintype "passive"))
      (node (ref "R26") (pin "1") (pinfunction "1_1") (pintype "passive"))
      (node (ref "R30") (pin "2") (pinfunction "2_2") (pintype "passive"))
      (node (ref "U1") (pin "100") (pinfunction "VDD_100") (pintype "power_in"))
      (node (ref "U1") (pin "11") (pinfunction "VDD_11") (pintype "power_in"))
      (node (ref "U1") (pin "19") (pinfunction "VDD_19") (pintype "power_in"))
      (node (ref "U1") (pin "28") (pinfunction "VDD_28") (pintype "power_in"))
      (node (ref "U1") (pin "50") (pinfunction "VDD_50") (pintype "power_in"))
      (node (ref "U1") (pin "6") (pinfunction "VBAT_6") (pintype "power_in"))
      (node (ref "U1") (pin "75") (pinfunction "VDD_75") (pintype "power_in"))
      (node (ref "U2") (pin "16") (pinfunction "VDD3.3_16") (pintype "power_in"))
      (node (ref "U2") (pin "25") (pinfunction "VDD3.3_25") (pintype "power_in"))
      (node (ref "U2") (pin "30") (pinfunction "VDD3.3_30") (pintype "power_in"))
      (node (ref "U2") (pin "31") (pinfunction "REG_EN_31") (pintype "passive"))
      (node (ref "U2") (pin "6") (pinfunction "VDD3.3_6") (pintype "power_in"))
      (node (ref "U5") (pin "5") (pinfunction "VOUT_5") (pintype "passive"))
      (node (ref "U7") (pin "3") (pinfunction "VCC_3") (pintype "passive"))
    )
    (net (code "57") (name "3.3VA") (class "Default")
      (node (ref "C10") (pin "1") (pinfunction "1_1") (pintype "passive"))
      (node (ref "C9") (pin "1") (pinfunction "1_1") (pintype "passive"))
      (node (ref "L2") (pin "1") (pinfunction "1_1") (pintype "passive"))
      (node (ref "U1") (pin "22") (pinfunction "VDDA_22") (pintype "power_in"))
    )
    (net (code "58") (name "3.3VPA") (class "Default")
      (node (ref "C19") (pin "2") (pinfunction "2_2") (pintype "passive"))
      (node (ref "C20") (pin "2") (pinfunction "2_2") (pintype "passive"))
      (node (ref "C21") (pin "2") (pinfunction "2_2") (pintype "passive"))
      (node (ref "C22") (pin "2") (pinfunction "2_2") (pintype "passive"))
      (node (ref "C23") (pin "2") (pinfunction "2_2") (pintype "passive"))
      (node (ref "R22") (pin "1") (pinfunction "1_1") (pintype "passive"))
      (node (ref "U3") (pin "14") (pinfunction "VDD_14") (pintype "passive"))
      (node (ref "U3") (pin "16") (pinfunction "VDD_16") (pintype "passive"))
    )
    (net (code "59") (name "3.3VRF") (class "Default")
      (node (ref "C34") (pin "2") (pinfunction "2_2") (pintype "passive"))
      (node (ref "C35") (pin "2") (pinfunction "2_2") (pintype "passive"))
      (node (ref "C57") (pin "2") (pinfunction "2_2") (pintype "passive"))
      (node (ref "NRF24L01") (pin "15") (pinfunction "VDD_15") (pintype "passive"))
      (node (ref "NRF24L01") (pin "18") (pinfunction "VDD_18") (pintype "passive"))
      (node (ref "NRF24L01") (pin "7") (pinfunction "VDD_7") (pintype "passive"))
      (node (ref "R22") (pin "2") (pinfunction "2_2") (pintype "passive"))
      (node (ref "U9") (pin "5") (pinfunction "OUT_5") (pintype "passive"))
    )
    (net (code "60") (name "5V") (class "Default")
      (node (ref "C1") (pin "1") (pinfunction "1_1") (pintype "passive"))
      (node (ref "C2") (pin "1") (pinfunction "1_1") (pintype "passive"))
      (node (ref "C48") (pin "2") (pinfunction "2_2") (pintype "passive"))
      (node (ref "C49") (pin "2") (pinfunction "2_2") (pintype "passive"))
      (node (ref "C53") (pin "2") (pinfunction "2_2") (pintype "passive"))
      (node (ref "D1") (pin "2") (pinfunction "K_2") (pintype "passive"))
      (node (ref "D20") (pin "2") (pinfunction "K_2") (pintype "passive"))
      (node (ref "L1") (pin "1") (pinfunction "1_1") (pintype "passive"))
      (node (ref "P1") (pin "1") (pinfunction "1_1") (pintype "passive"))
      (node (ref "P1") (pin "2") (pinfunction "2_2") (pintype "passive"))
      (node (ref "U2") (pin "4") (pinfunction "VBUS_4") (pintype "power_in"))
      (node (ref "U5") (pin "1") (pinfunction "VIN_1") (pintype "passive"))
      (node (ref "U5") (pin "3") (pinfunction "CE_3") (pintype "passive"))
      (node (ref "U6") (pin "1") (pinfunction "IN_1") (pintype "passive"))
      (node (ref "U9") (pin "1") (pinfunction "IN_1") (pintype "passive"))
      (node (ref "U9") (pin "3") (pinfunction "EN_3") (pintype "passive"))
    )
    (net (code "61") (name "GND") (class "Default")
      (node (ref "C1") (pin "2") (pinfunction "2_2") (pintype "passive"))
      (node (ref "C10") (pin "2") (pinfunction "2_2") (pintype "passive"))
      (node (ref "C11") (pin "1") (pinfunction "1_1") (pintype "passive"))
      (node (ref "C12") (pin "1") (pinfunction "1_1") (pintype "passive"))
      (node (ref "C13") (pin "1") (pinfunction "1_1") (pintype "passive"))
      (node (ref "C14") (pin "1") (pinfunction "1_1") (pintype "passive"))
      (node (ref "C15") (pin "1") (pinfunction "1_1") (pintype "passive"))
      (node (ref "C16") (pin "1") (pinfunction "1_1") (pintype "passive"))
      (node (ref "C17") (pin "1") (pinfunction "1_1") (pintype "passive"))
      (node (ref "C18") (pin "2") (pinfunction "2_2") (pintype "passive"))
      (node (ref "C19") (pin "1") (pinfunction "1_1") (pintype "passive"))
      (node (ref "C2") (pin "2") (pinfunction "2_2") (pintype "passive"))
      (node (ref "C20") (pin "1") (pinfunction "1_1") (pintype "passive"))
      (node (ref "C21") (pin "1") (pinfunction "1_1") (pintype "passive"))
      (node (ref "C22") (pin "1") (pinfunction "1_1") (pintype "passive"))
      (node (ref "C23") (pin "1") (pinfunction "1_1") (pintype "passive"))
      (node (ref "C24") (pin "1") (pinfunction "1_1") (pintype "passive"))
      (node (ref "C25") (pin "1") (pinfunction "1_1") (pintype "passive"))
      (node (ref "C26") (pin "1") (pinfunction "1_1") (pintype "passive"))
      (node (ref "C27") (pin "1") (pinfunction "1_1") (pintype "passive"))
      (node (ref "C28") (pin "1") (pinfunction "1_1") (pintype "passive"))
      (node (ref "C29") (pin "1") (pinfunction "1_1") (pintype "passive"))
      (node (ref "C30") (pin "1") (pinfunction "1_1") (pintype "passive"))
      (node (ref "C31") (pin "1") (pinfunction "1_1") (pintype "passive"))
      (node (ref "C32") (pin "1") (pinfunction "1_1") (pintype "passive"))
      (node (ref "C33") (pin "1") (pinfunction "1_1") (pintype "passive"))
      (node (ref "C34") (pin "1") (pinfunction "1_1") (pintype "passive"))
      (node (ref "C35") (pin "1") (pinfunction "1_1") (pintype "passive"))
      (node (ref "C36") (pin "1") (pinfunction "1_1") (pintype "passive"))
      (node (ref "C37") (pin "1") (pinfunction "1_1") (pintype "passive"))
      (node (ref "C38") (pin "1") (pinfunction "1_1") (pintype "passive"))
      (node (ref "C4") (pin "1") (pinfunction "1_1") (pintype "passive"))
      (node (ref "C40") (pin "1") (pinfunction "1_1") (pintype "passive"))
      (node (ref "C41") (pin "1") (pinfunction "1_1") (pintype "passive"))
      (node (ref "C42") (pin "1") (pinfunction "1_1") (pintype "passive"))
      (node (ref "C43") (pin "1") (pinfunction "1_1") (pintype "passive"))
      (node (ref "C44") (pin "1") (pinfunction "1_1") (pintype "passive"))
      (node (ref "C45") (pin "1") (pinfunction "1_1") (pintype "passive"))
      (node (ref "C46") (pin "1") (pinfunction "1_1") (pintype "passive"))
      (node (ref "C47") (pin "1") (pinfunction "1_1") (pintype "passive"))
      (node (ref "C48") (pin "1") (pinfunction "1_1") (pintype "passive"))
      (node (ref "C49") (pin "1") (pinfunction "1_1") (pintype "passive"))
      (node (ref "C5") (pin "1") (pinfunction "1_1") (pintype "passive"))
      (node (ref "C50") (pin "1") (pinfunction "1_1") (pintype "passive"))
      (node (ref "C51") (pin "1") (pinfunction "1_1") (pintype "passive"))
      (node (ref "C52") (pin "1") (pinfunction "1_1") (pintype "passive"))
      (node (ref "C53") (pin "1") (pinfunction "1_1") (pintype "passive"))
      (node (ref "C54") (pin "2") (pinfunction "2_2") (pintype "passive"))
      (node (ref "C55") (pin "2") (pinfunction "2_2") (pintype "passive"))
      (node (ref "C56") (pin "2") (pinfunction "2_2") (pintype "passive"))
      (node (ref "C57") (pin "1") (pinfunction "1_1") (pintype "passive"))
      (node (ref "C58") (pin "1") (pinfunction "1_1") (pintype "passive"))
      (node (ref "C59") (pin "2") (pinfunction "2_2") (pintype "passive"))
      (node (ref "C6") (pin "1") (pinfunction "1_1") (pintype "passive"))
      (node (ref "C7") (pin "1") (pinfunction "1_1") (pintype "passive"))
      (node (ref "C8") (pin "1") (pinfunction "1_1") (pintype "passive"))
      (node (ref "C9") (pin "2") (pinfunction "2_2") (pintype "passive"))
      (node (ref "D1") (pin "1") (pinfunction "A_1") (pintype "passive"))
      (node (ref "D10") (pin "1") (pinfunction "A_1") (pintype "passive"))
      (node (ref "D11") (pin "1") (pinfunction "A_1") (pintype "passive"))
      (node (ref "D12") (pin "1") (pinfunction "A_1") (pintype "passive"))
      (node (ref "D13") (pin "1") (pinfunction "A_1") (pintype "passive"))
      (node (ref "D14") (pin "1") (pinfunction "A_1") (pintype "passive"))
      (node (ref "D15") (pin "1") (pinfunction "A_1") (pintype "passive"))
      (node (ref "D16") (pin "1") (pinfunction "A_1") (pintype "passive"))
      (node (ref "D17") (pin "1") (pinfunction "A_1") (pintype "passive"))
      (node (ref "D19") (pin "1") (pinfunction "A_1") (pintype "passive"))
      (node (ref "D2") (pin "1") (pinfunction "A_1") (pintype "passive"))
      (node (ref "D3") (pin "1") (pinfunction "A_1") (pintype "passive"))
      (node (ref "D4") (pin "1") (pinfunction "A_1") (pintype "passive"))
      (node (ref "D5") (pin "1") (pinfunction "A_1") (pintype "passive"))
      (node (ref "D6") (pin "1") (pinfunction "A_1") (pintype "passive"))
      (node (ref "D7") (pin "1") (pinfunction "A_1") (pintype "passive"))
      (node (ref "D8") (pin "1") (pinfunction "A_1") (pintype "passive"))
      (node (ref "D9") (pin "1") (pinfunction "A_1") (pintype "passive"))
      (node (ref "E1") (pin "2") (pinfunction "GND_2") (pintype "passive"))
      (node (ref "H5") (pin "1") (pinfunction "1_1") (pintype "passive"))
      (node (ref "NRF24L01") (pin "0") (pinfunction "PAD_0") (pintype "passive"))
      (node (ref "NRF24L01") (pin "14") (pinfunction "VSS_14") (pintype "passive"))
      (node (ref "NRF24L01") (pin "17") (pinfunction "VSS_17") (pintype "passive"))
      (node (ref "NRF24L01") (pin "20") (pinfunction "VSS_20") (pintype "passive"))
      (node (ref "NRF24L01") (pin "8") (pinfunction "VSS_8") (pintype "passive"))
      (node (ref "P1") (pin "17") (pinfunction "17_17") (pintype "passive"))
      (node (ref "P1") (pin "5") (pinfunction "5_5") (pintype "passive"))
      (node (ref "P1") (pin "6") (pinfunction "6_6") (pintype "passive"))
      (node (ref "P2") (pin "A1") (pinfunction "GND_A1") (pintype "passive"))
      (node (ref "P2") (pin "A12") (pinfunction "GND_A12") (pintype "passive"))
      (node (ref "P2") (pin "B1") (pinfunction "GND_B1") (pintype "passive"))
      (node (ref "P2") (pin "B12") (pinfunction "GND_B12") (pintype "passive"))
      (node (ref "R16") (pin "1") (pinfunction "1_1") (pintype "passive"))
      (node (ref "R20") (pin "1") (pinfunction "1_1") (pintype "passive"))
      (node (ref "R21") (pin "2") (pinfunction "2_2") (pintype "passive"))
      (node (ref "R24") (pin "1") (pinfunction "1_1") (pintype "passive"))
      (node (ref "R25") (pin "2") (pinfunction "2_2") (pintype "passive"))
      (node (ref "R29") (pin "1") (pinfunction "1_1") (pintype "passive"))
      (node (ref "R9") (pin "2") (pinfunction "2_2") (pintype "passive"))
      (node (ref "T1") (pin "2") (pinfunction "E_2") (pintype "passive"))
      (node (ref "U1") (pin "10") (pinfunction "VSS_10") (pintype "power_in"))
      (node (ref "U1") (pin "20") (pinfunction "VSSA_20") (pintype "power_in"))
      (node (ref "U1") (pin "27") (pinfunction "VSS_27") (pintype "power_in"))
      (node (ref "U1") (pin "74") (pinfunction "VSS_74") (pintype "power_in"))
      (node (ref "U1") (pin "99") (pinfunction "VSS_99") (pintype "power_in"))
      (node (ref "U2") (pin "0") (pinfunction "GND_FLAG_0") (pintype "power_in"))
      (node (ref "U2") (pin "1") (pinfunction "GND_1") (pintype "power_in"))
      (node (ref "U2") (pin "2") (pinfunction "GND_2") (pintype "power_in"))
      (node (ref "U3") (pin "0") (pinfunction "PAD_0") (pintype "passive"))
      (node (ref "U3") (pin "1") (pinfunction "NC_1") (pintype "passive"))
      (node (ref "U3") (pin "11") (pinfunction "GND_11") (pintype "passive"))
      (node (ref "U3") (pin "12") (pinfunction "NC_12") (pintype "passive"))
      (node (ref "U3") (pin "15") (pinfunction "NC_15") (pintype "passive"))
      (node (ref "U3") (pin "2") (pinfunction "GND_2") (pintype "passive"))
      (node (ref "U3") (pin "3") (pinfunction "GND_3") (pintype "passive"))
      (node (ref "U3") (pin "7") (pinfunction "NC_7") (pintype "passive"))
      (node (ref "U3") (pin "8") (pinfunction "GND_8") (pintype "passive"))
      (node (ref "U3") (pin "9") (pinfunction "GND_9") (pintype "passive"))
      (node (ref "U5") (pin "2") (pinfunction "VSS_2") (pintype "passive"))
      (node (ref "U6") (pin "3") (pinfunction "GND_3") (pintype "passive"))
      (node (ref "U7") (pin "2") (pinfunction "GND_2") (pintype "passive"))
      (node (ref "U7") (pin "8") (pinfunction "Rs_8") (pintype "passive"))
      (node (ref "U8") (pin "15") (pinfunction "GND_15") (pintype "passive"))
      (node (ref "U9") (pin "2") (pinfunction "GND_2") (pintype "passive"))
      (node (ref "XT3") (pin "2") (pinfunction "2_2") (pintype "passive"))
      (node (ref "XT3") (pin "4") (pinfunction "4_4") (pintype "passive"))
    )
    (net (code "62") (name "Net-(C4-Pad2)") (class "Default")
      (node (ref "C4") (pin "2") (pinfunction "2_2") (pintype "passive"))
      (node (ref "P2") (pin "1") (pinfunction "SHELL_1") (pintype "passive"))
      (node (ref "P2") (pin "2") (pinfunction "SHELL_2") (pintype "passive"))
      (node (ref "P2") (pin "3") (pinfunction "SHELL_3") (pintype "passive"))
      (node (ref "P2") (pin "4") (pinfunction "SHELL_4") (pintype "passive"))
      (node (ref "R16") (pin "2") (pinfunction "2_2") (pintype "passive"))
    )
    (net (code "63") (name "Net-(C12-Pad2)") (class "Default")
      (node (ref "C12") (pin "2") (pinfunction "2_2") (pintype "passive"))
      (node (ref "U2") (pin "15") (pinfunction "VDD1.8_15") (pintype "power_in"))
    )
    (net (code "64") (name "Net-(C13-Pad2)") (class "Default")
      (node (ref "C13") (pin "2") (pinfunction "2_2") (pintype "passive"))
      (node (ref "U2") (pin "26") (pinfunction "VDD1.8_26") (pintype "power_in"))
    )
    (net (code "65") (name "Net-(C39-Pad2)") (class "Default")
      (node (ref "C39") (pin "2") (pinfunction "2_2") (pintype "passive"))
      (node (ref "L4") (pin "2") (pinfunction "2_2") (pintype "passive"))
    )
    (net (code "66") (name "Net-(C58-Pad2)") (class "Default")
      (node (ref "C58") (pin "2") (pinfunction "2_2") (pintype "passive"))
      (node (ref "R31") (pin "1") (pinfunction "1_1") (pintype "passive"))
      (node (ref "R32") (pin "1") (pinfunction "1_1") (pintype "passive"))
    )
    (net (code "67") (name "Net-(D18-A)") (class "Default")
      (node (ref "Buzzer1") (pin "2") (pinfunction "2_2") (pintype "passive"))
      (node (ref "D18") (pin "1") (pinfunction "A_1") (pintype "passive"))
      (node (ref "T1") (pin "3") (pinfunction "C_3") (pintype "passive"))
    )
    (net (code "68") (name "Net-(D20-A)") (class "Default")
      (node (ref "D20") (pin "1") (pinfunction "A_1") (pintype "passive"))
      (node (ref "R29") (pin "2") (pinfunction "2_2") (pintype "passive"))
    )
    (net (code "69") (name "Net-(E1-ANT)") (class "Default")
      (node (ref "C42") (pin "2") (pinfunction "2_2") (pintype "passive"))
      (node (ref "E1") (pin "1") (pinfunction "ANT_1") (pintype "passive"))
      (node (ref "L3") (pin "2") (pinfunction "2_2") (pintype "passive"))
    )
    (net (code "70") (name "Net-(F1-Pad1)") (class "Default")
      (node (ref "F1") (pin "1") (pinfunction "1_1") (pintype "passive"))
      (node (ref "L1") (pin "2") (pinfunction "2_2") (pintype "passive"))
    )
    (net (code "71") (name "Net-(F1-Pad2)") (class "Default")
      (node (ref "F1") (pin "2") (pinfunction "2_2") (pintype "passive"))
      (node (ref "P2") (pin "A4") (pinfunction "VBUS_A4") (pintype "passive"))
      (node (ref "P2") (pin "A9") (pinfunction "VBUS_A9") (pintype "passive"))
      (node (ref "P2") (pin "B4") (pinfunction "VBUS_B4") (pintype "passive"))
      (node (ref "P2") (pin "B9") (pinfunction "VBUS_B9") (pintype "passive"))
    )
    (net (code "72") (name "Net-(NRF24L01-ANT1)") (class "Default")
      (node (ref "L5") (pin "1") (pinfunction "1_1") (pintype "passive"))
      (node (ref "L6") (pin "1") (pinfunction "1_1") (pintype "passive"))
      (node (ref "NRF24L01") (pin "12") (pinfunction "ANT1_12") (pintype "passive"))
    )
    (net (code "73") (name "Net-(NRF24L01-ANT2)") (class "Default")
      (node (ref "L4") (pin "1") (pinfunction "1_1") (pintype "passive"))
      (node (ref "L5") (pin "2") (pinfunction "2_2") (pintype "passive"))
      (node (ref "NRF24L01") (pin "13") (pinfunction "ANT2_13") (pintype "passive"))
    )
    (net (code "74") (name "Net-(NRF24L01-DVDD)") (class "Default")
      (node (ref "C18") (pin "1") (pinfunction "1_1") (pintype "passive"))
      (node (ref "NRF24L01") (pin "19") (pinfunction "DVDD_19") (pintype "passive"))
    )
    (net (code "75") (name "Net-(NRF24L01-IREF)") (class "Default")
      (node (ref "NRF24L01") (pin "16") (pinfunction "IREF_16") (pintype "passive"))
      (node (ref "R21") (pin "1") (pinfunction "1_1") (pintype "passive"))
    )
    (net (code "76") (name "Net-(NRF24L01-VCC_PA)") (class "Default")
      (node (ref "C44") (pin "2") (pinfunction "2_2") (pintype "passive"))
      (node (ref "C45") (pin "2") (pinfunction "2_2") (pintype "passive"))
      (node (ref "L6") (pin "2") (pinfunction "2_2") (pintype "passive"))
      (node (ref "NRF24L01") (pin "11") (pinfunction "VCC_PA_11") (pintype "passive"))
      (node (ref "R27") (pin "2") (pinfunction "2_2") (pintype "passive"))
    )
    (net (code "77") (name "Net-(NRF24L01-XC1)") (class "Default")
      (node (ref "C51") (pin "2") (pinfunction "2_2") (pintype "passive"))
      (node (ref "NRF24L01") (pin "10") (pinfunction "XC1_10") (pintype "passive"))
      (node (ref "XT3") (pin "3") (pinfunction "3_3") (pintype "passive"))
    )
    (net (code "78") (name "Net-(NRF24L01-XC2)") (class "Default")
      (node (ref "C50") (pin "2") (pinfunction "2_2") (pintype "passive"))
      (node (ref "NRF24L01") (pin "9") (pinfunction "XC2_9") (pintype "passive"))
      (node (ref "XT3") (pin "1") (pinfunction "1_1") (pintype "passive"))
    )
    (net (code "79") (name "Net-(T1-B)") (class "Default")
      (node (ref "R23") (pin "2") (pinfunction "2_2") (pintype "passive"))
      (node (ref "R25") (pin "1") (pinfunction "1_1") (pintype "passive"))
      (node (ref "T1") (pin "1") (pinfunction "B_1") (pintype "passive"))
    )
    (net (code "80") (name "Net-(U1B-VCAP1)") (class "Default")
      (node (ref "C17") (pin "2") (pinfunction "2_2") (pintype "passive"))
      (node (ref "U1") (pin "49") (pinfunction "VCAP1_49") (pintype "power_in"))
    )
    (net (code "81") (name "Net-(U1B-VCAP2)") (class "Default")
      (node (ref "C16") (pin "2") (pinfunction "2_2") (pintype "passive"))
      (node (ref "U1") (pin "73") (pinfunction "VCAP2_73") (pintype "power_in"))
    )
    (net (code "82") (name "Net-(U1C-BOOT0)") (class "Default")
      (node (ref "R24") (pin "2") (pinfunction "2_2") (pintype "passive"))
      (node (ref "U1") (pin "94") (pinfunction "BOOT0_94") (pintype "input"))
    )
    (net (code "83") (name "Net-(U1C-OSC_IN)") (class "Default")
      (node (ref "C38") (pin "2") (pinfunction "2_2") (pintype "passive"))
      (node (ref "U1") (pin "12") (pinfunction "OSC_IN_12") (pintype "bidirectional"))
      (node (ref "XT2") (pin "2") (pinfunction "2_2") (pintype "passive"))
    )
    (net (code "84") (name "Net-(U1C-OSC_OUT)") (class "Default")
      (node (ref "C37") (pin "2") (pinfunction "2_2") (pintype "passive"))
      (node (ref "U1") (pin "13") (pinfunction "OSC_OUT_13") (pintype "bidirectional"))
      (node (ref "XT2") (pin "1") (pinfunction "1_1") (pintype "passive"))
    )
    (net (code "85") (name "Net-(U2-RBIAS)") (class "Default")
      (node (ref "R20") (pin "2") (pinfunction "2_2") (pintype "passive"))
      (node (ref "U2") (pin "32") (pinfunction "RBIAS_32") (pintype "passive"))
    )
    (net (code "86") (name "Net-(U2-RESET)") (class "Default")
      (node (ref "C3") (pin "1") (pinfunction "1_1") (pintype "passive"))
      (node (ref "R9") (pin "1") (pinfunction "1_1") (pintype "passive"))
      (node (ref "U2") (pin "9") (pinfunction "RESET_9") (pintype "input"))
    )
    (net (code "87") (name "Net-(U2-VDDA1.8)") (class "Default")
      (node (ref "C14") (pin "2") (pinfunction "2_2") (pintype "passive"))
      (node (ref "U2") (pin "29") (pinfunction "VDDA1.8_29") (pintype "power_in"))
    )
    (net (code "88") (name "Net-(U2-XI)") (class "Default")
      (node (ref "C11") (pin "2") (pinfunction "2_2") (pintype "passive"))
      (node (ref "R18") (pin "2") (pinfunction "2_2") (pintype "passive"))
      (node (ref "U2") (pin "28") (pinfunction "XI_28") (pintype "passive"))
      (node (ref "XT1") (pin "2") (pinfunction "2_2") (pintype "passive"))
    )
    (net (code "89") (name "Net-(U2-XO)") (class "Default")
      (node (ref "C15") (pin "2") (pinfunction "2_2") (pintype "passive"))
      (node (ref "R18") (pin "1") (pinfunction "1_1") (pintype "passive"))
      (node (ref "U2") (pin "27") (pinfunction "XO_27") (pintype "passive"))
      (node (ref "XT1") (pin "1") (pinfunction "1_1") (pintype "passive"))
    )
    (net (code "90") (name "Net-(U3-ANT)") (class "Default")
      (node (ref "C41") (pin "2") (pinfunction "2_2") (pintype "passive"))
      (node (ref "L3") (pin "1") (pinfunction "1_1") (pintype "passive"))
      (node (ref "U3") (pin "10") (pinfunction "ANT_10") (pintype "passive"))
    )
    (net (code "91") (name "Net-(U3-RXEN)") (class "Default")
      (node (ref "R28") (pin "2") (pinfunction "2_2") (pintype "passive"))
      (node (ref "U3") (pin "6") (pinfunction "RXEN_6") (pintype "passive"))
    )
    (net (code "92") (name "Net-(U3-TXEN)") (class "Default")
      (node (ref "R27") (pin "1") (pinfunction "1_1") (pintype "passive"))
      (node (ref "U3") (pin "5") (pinfunction "TXEN_5") (pintype "passive"))
    )
    (net (code "93") (name "Net-(U3-TXRX)") (class "Default")
      (node (ref "C39") (pin "1") (pinfunction "1_1") (pintype "passive"))
      (node (ref "C43") (pin "2") (pinfunction "2_2") (pintype "passive"))
      (node (ref "U3") (pin "4") (pinfunction "TXRX_4") (pintype "passive"))
    )
    (net (code "94") (name "Net-(U7-CANH)") (class "Default")
      (node (ref "R31") (pin "2") (pinfunction "2_2") (pintype "passive"))
      (node (ref "U7") (pin "7") (pinfunction "CANH_7") (pintype "passive"))
    )
    (net (code "95") (name "Net-(U7-CANL)") (class "Default")
      (node (ref "R32") (pin "2") (pinfunction "2_2") (pintype "passive"))
      (node (ref "U7") (pin "6") (pinfunction "CANL_6") (pintype "passive"))
    )
    (net (code "96") (name "Net-(U8-C1+)") (class "Default")
      (node (ref "C60") (pin "2") (pinfunction "2_2") (pintype "passive"))
      (node (ref "U8") (pin "1") (pinfunction "C1+_1") (pintype "passive"))
    )
    (net (code "97") (name "Net-(U8-C1-)") (class "Default")
      (node (ref "C60") (pin "1") (pinfunction "1_1") (pintype "passive"))
      (node (ref "U8") (pin "3") (pinfunction "C1-_3") (pintype "passive"))
    )
    (net (code "98") (name "Net-(U8-C2+)") (class "Default")
      (node (ref "C61") (pin "2") (pinfunction "2_2") (pintype "passive"))
      (node (ref "U8") (pin "4") (pinfunction "C2+_4") (pintype "passive"))
    )
    (net (code "99") (name "Net-(U8-C2-)") (class "Default")
      (node (ref "C61") (pin "1") (pinfunction "1_1") (pintype "passive"))
      (node (ref "U8") (pin "5") (pinfunction "C2-_5") (pintype "passive"))
    )
    (net (code "100") (name "Net-(U8-V+)") (class "Default")
      (node (ref "C56") (pin "1") (pinfunction "1_1") (pintype "passive"))
      (node (ref "U8") (pin "2") (pinfunction "V+_2") (pintype "passive"))
    )
    (net (code "101") (name "Net-(U8-V-)") (class "Default")
      (node (ref "C59") (pin "1") (pinfunction "1_1") (pintype "passive"))
      (node (ref "U8") (pin "6") (pinfunction "V-_6") (pintype "passive"))
    )
    (net (code "102") (name "Net-(U8-VCC)") (class "Default")
      (node (ref "C55") (pin "1") (pinfunction "1_1") (pintype "passive"))
      (node (ref "R30") (pin "1") (pinfunction "1_1") (pintype "passive"))
      (node (ref "U8") (pin "16") (pinfunction "VCC_16") (pintype "passive"))
    )
    (net (code "103") (name "unconnected-(H1-Pad1)") (class "Default")
      (node (ref "H1") (pin "1") (pinfunction "1_1") (pintype "passive"))
    )
    (net (code "104") (name "unconnected-(H4-Pad1)") (class "Default")
      (node (ref "H4") (pin "1") (pinfunction "1_1") (pintype "passive"))
    )
    (net (code "105") (name "unconnected-(P1-Pad7)") (class "Default")
      (node (ref "P1") (pin "7") (pinfunction "7_7") (pintype "passive+no_connect"))
    )
    (net (code "106") (name "unconnected-(P1-Pad9)") (class "Default")
      (node (ref "P1") (pin "9") (pinfunction "9_9") (pintype "passive+no_connect"))
    )
    (net (code "107") (name "unconnected-(P1-Pad11)") (class "Default")
      (node (ref "P1") (pin "11") (pinfunction "11_11") (pintype "passive+no_connect"))
    )
    (net (code "108") (name "unconnected-(P1-Pad12)") (class "Default")
      (node (ref "P1") (pin "12") (pinfunction "12_12") (pintype "passive+no_connect"))
    )
    (net (code "109") (name "unconnected-(P1-Pad13)") (class "Default")
      (node (ref "P1") (pin "13") (pinfunction "13_13") (pintype "passive+no_connect"))
    )
    (net (code "110") (name "unconnected-(P1-Pad14)") (class "Default")
      (node (ref "P1") (pin "14") (pinfunction "14_14") (pintype "passive+no_connect"))
    )
    (net (code "111") (name "unconnected-(P1-Pad15)") (class "Default")
      (node (ref "P1") (pin "15") (pinfunction "15_15") (pintype "passive+no_connect"))
    )
    (net (code "112") (name "unconnected-(P1-Pad16)") (class "Default")
      (node (ref "P1") (pin "16") (pinfunction "16_16") (pintype "passive+no_connect"))
    )
    (net (code "113") (name "unconnected-(P1-Pad18)") (class "Default")
      (node (ref "P1") (pin "18") (pinfunction "18_18") (pintype "passive+no_connect"))
    )
    (net (code "114") (name "unconnected-(P1-Pad20)") (class "Default")
      (node (ref "P1") (pin "20") (pinfunction "20_20") (pintype "passive+no_connect"))
    )
    (net (code "115") (name "unconnected-(P1-Pad22)") (class "Default")
      (node (ref "P1") (pin "22") (pinfunction "22_22") (pintype "passive+no_connect"))
    )
    (net (code "116") (name "unconnected-(P1-Pad24)") (class "Default")
      (node (ref "P1") (pin "24") (pinfunction "24_24") (pintype "passive+no_connect"))
    )
    (net (code "117") (name "unconnected-(P1-Pad26)") (class "Default")
      (node (ref "P1") (pin "26") (pinfunction "26_26") (pintype "passive+no_connect"))
    )
    (net (code "118") (name "unconnected-(P1-Pad28)") (class "Default")
      (node (ref "P1") (pin "28") (pinfunction "28_28") (pintype "passive+no_connect"))
    )
    (net (code "119") (name "unconnected-(P1-Pad30)") (class "Default")
      (node (ref "P1") (pin "30") (pinfunction "30_30") (pintype "passive+no_connect"))
    )
    (net (code "120") (name "unconnected-(P1-Pad31)") (class "Default")
      (node (ref "P1") (pin "31") (pinfunction "31_31") (pintype "passive+no_connect"))
    )
    (net (code "121") (name "unconnected-(P1-Pad34)") (class "Default")
      (node (ref "P1") (pin "34") (pinfunction "34_34") (pintype "passive+no_connect"))
    )
    (net (code "122") (name "unconnected-(P1-Pad35)") (class "Default")
      (node (ref "P1") (pin "35") (pinfunction "35_35") (pintype "passive+no_connect"))
    )
    (net (code "123") (name "unconnected-(P1-Pad37)") (class "Default")
      (node (ref "P1") (pin "37") (pinfunction "37_37") (pintype "passive+no_connect"))
    )
    (net (code "124") (name "unconnected-(P1-Pad40)") (class "Default")
      (node (ref "P1") (pin "40") (pinfunction "40_40") (pintype "passive+no_connect"))
    )
    (net (code "125") (name "unconnected-(P1-Pad42)") (class "Default")
      (node (ref "P1") (pin "42") (pinfunction "42_42") (pintype "passive+no_connect"))
    )
    (net (code "126") (name "unconnected-(P1-Pad44)") (class "Default")
      (node (ref "P1") (pin "44") (pinfunction "44_44") (pintype "passive+no_connect"))
    )
    (net (code "127") (name "unconnected-(P1-Pad52)") (class "Default")
      (node (ref "P1") (pin "52") (pinfunction "52_52") (pintype "passive+no_connect"))
    )
    (net (code "128") (name "unconnected-(P2-CC1-PadA5)") (class "Default")
      (node (ref "P2") (pin "A5") (pinfunction "CC1_A5") (pintype "passive+no_connect"))
    )
    (net (code "129") (name "unconnected-(P2-CC2-PadB5)") (class "Default")
      (node (ref "P2") (pin "B5") (pinfunction "CC2_B5") (pintype "passive+no_connect"))
    )
    (net (code "130") (name "unconnected-(P2-SBU1-PadA8)") (class "Default")
      (node (ref "P2") (pin "A8") (pinfunction "SBU1_A8") (pintype "passive+no_connect"))
    )
    (net (code "131") (name "unconnected-(P2-SBU2-PadB8)") (class "Default")
      (node (ref "P2") (pin "B8") (pinfunction "SBU2_B8") (pintype "passive+no_connect"))
    )
    (net (code "132") (name "unconnected-(U2-CPEN-Pad3)") (class "Default")
      (node (ref "U2") (pin "3") (pinfunction "CPEN_3") (pintype "power_in+no_connect"))
    )
    (net (code "133") (name "unconnected-(U2-EXTVBUS-Pad10)") (class "Default")
      (node (ref "U2") (pin "10") (pinfunction "EXTVBUS_10") (pintype "passive+no_connect"))
    )
    (net (code "134") (name "unconnected-(U2-ID-Pad5)") (class "Default")
      (node (ref "U2") (pin "5") (pinfunction "ID_5") (pintype "passive+no_connect"))
    )
    (net (code "135") (name "unconnected-(U3-DNC-Pad13)") (class "Default")
      (node (ref "U3") (pin "13") (pinfunction "DNC_13") (pintype "passive+no_connect"))
    )
    (net (code "136") (name "unconnected-(U5-NC-Pad4)") (class "Default")
      (node (ref "U5") (pin "4") (pinfunction "NC_4") (pintype "passive"))
    )
    (net (code "137") (name "unconnected-(U7-Vref-Pad5)") (class "Default")
      (node (ref "U7") (pin "5") (pinfunction "Vref_5") (pintype "passive+no_connect"))
    )
    (net (code "138") (name "unconnected-(U8-R2IN-Pad8)") (class "Default")
      (node (ref "U8") (pin "8") (pinfunction "R2IN_8") (pintype "passive+no_connect"))
    )
    (net (code "139") (name "unconnected-(U8-T2IN-Pad10)") (class "Default")
      (node (ref "U8") (pin "10") (pinfunction "T2IN_10") (pintype "passive+no_connect"))
    )
    (net (code "140") (name "unconnected-(U8-T2OUT-Pad7)") (class "Default")
      (node (ref "U8") (pin "7") (pinfunction "T2OUT_7") (pintype "passive+no_connect"))
    )
    (net (code "141") (name "unconnected-(U8-T2OUT-Pad9)") (class "Default")
      (node (ref "U8") (pin "9") (pinfunction "T2OUT_9") (pintype "passive+no_connect"))
    )
    (net (code "142") (name "unconnected-(U9-NC-Pad4)") (class "Default")
      (node (ref "U9") (pin "4") (pinfunction "NC_4") (pintype "passive+no_connect"))
    )
  )
)
